# Power_Unit.net
KiCad netlist of a schematic drawn in Altium Designer
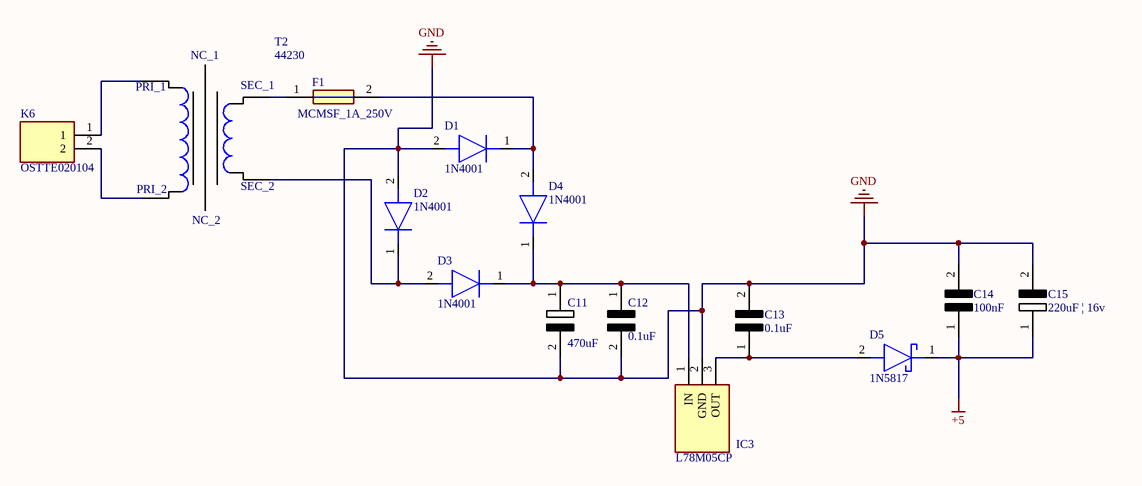
[diagram p0: Power_Unit.SchDoc]

(export (version "E")
  (design (tool "Eeschema 10.0.6"))
  (components
    (comp (ref "C11")
      (value "470uF")
      (footprint "C0805")
      (description "0805 ceramic capacitor")
      (fields
        (field (name "MANUFACTURER_PART_NUMBER") "GRM188R71H103KA01D")
        (field (name "MOUSER PART NUMBER") "81-GRM39X103K50D")
      )
      (libsource (lib "") (part "elektrolytischeC0805_1"))
    )
    (comp (ref "C12")
      (value "0.1uF")
      (footprint "C0805")
      (description "0805 ceramic capacitor")
      (fields
        (field (name "MANUFACTURER_PART_NUMBER") "GRM188R71H103KA01D")
        (field (name "MOUSER PART NUMBER") "81-GRM39X103K50D")
      )
      (libsource (lib "Schlib1") (part "KeramischeC0805_1"))
    )
    (comp (ref "C13")
      (value "0.1uF")
      (footprint "C0805")
      (description "0805 ceramic capacitor")
      (fields
        (field (name "MANUFACTURER_PART_NUMBER") "GRM188R71H103KA01D")
        (field (name "MOUSER PART NUMBER") "81-GRM39X103K50D")
      )
      (libsource (lib "") (part "KeramischeC0805_1_1"))
    )
    (comp (ref "C14")
      (value "100nF")
      (footprint "C0805")
      (description "0805 ceramic capacitor")
      (fields
        (field (name "MANUFACTURER_PART_NUMBER") "GRM188R71H103KA01D")
        (field (name "MOUSER PART NUMBER") "81-GRM39X103K50D")
      )
      (libsource (lib "") (part "KeramischeC0805_1_1"))
    )
    (comp (ref "C15")
      (value "220uF ¦ 16v")
      (footprint "C0805")
      (description "0805 ceramic capacitor")
      (fields
        (field (name "MANUFACTURER_PART_NUMBER") "GRM188R71H103KA01D")
        (field (name "MOUSER PART NUMBER") "81-GRM39X103K50D")
      )
      (libsource (lib "Schlib1") (part "elektrolytischeC0805"))
    )
    (comp (ref "D1")
      (value "1N4001")
      (footprint "SamacSys:DIOAD1405W86L465D235")
      (description "Diode")
      (libsource (lib "Schlib1") (part "1N4001"))
    )
    (comp (ref "D2")
      (value "1N4001")
      (footprint "SamacSys:DIOAD1405W86L465D235")
      (description "Diode")
      (libsource (lib "Schlib1") (part "1N4001"))
    )
    (comp (ref "D3")
      (value "1N4001")
      (footprint "SamacSys:DIOAD1405W86L465D235")
      (description "Diode")
      (libsource (lib "Schlib1") (part "1N4001"))
    )
    (comp (ref "D4")
      (value "1N4001")
      (footprint "SamacSys:DIOAD1405W86L465D235")
      (description "Diode")
      (libsource (lib "Schlib1") (part "1N4001"))
    )
    (comp (ref "D5")
      (value "1N5817")
      (footprint "1n5817_footprint")
      (description "Schottky Diode")
      (libsource (lib "Schlib1") (part "1N5817"))
    )
    (comp (ref "F1")
      (value "MCMSF_1A_250V")
      (footprint "SamacSys:MCMSF1A250V")
      (description "Fuse")
      (fields (field (name "MANUFACTURER_PART_NUMBER") "MCMSF 1A 250V"))
      (libsource (lib "Schlib1") (part "MCMSF_1A_250V"))
    )
    (comp (ref "IC3")
      (value "L78M05CP")
      (footprint "SamacSys:TO255P460X1020X2030-3P")
      (description "Integrated Circuit")
      (fields (field (name "MOUSER PART NUMBER") "511-L78M05CP"))
      (libsource (lib "Schlib1") (part "L78M05CP"))
    )
    (comp (ref "K6")
      (value "OSTTE020104")
      (footprint "SamacSys:OSTTE020104")
      (description "Connector")
      (libsource (lib "Schlib1") (part "OSTTE020104"))
    )
    (comp (ref "T2")
      (value "44230")
      (footprint "SamacSys:44230")
      (description "Transformer")
      (libsource (lib "Schlib1") (part "44230"))
    )
  )
  (nets
    (net (code "1") (name "+5") (class "Default")
      (node (ref "C14") (pin "1") (pinfunction "1_1") (pintype "passive"))
      (node (ref "C15") (pin "1") (pinfunction "1_1") (pintype "passive"))
      (node (ref "D5") (pin "1") (pinfunction "K_1") (pintype "passive"))
    )
    (net (code "2") (name "GND") (class "Default")
      (node (ref "C11") (pin "2") (pinfunction "2_2") (pintype "passive"))
      (node (ref "C12") (pin "2") (pinfunction "2_2") (pintype "passive"))
      (node (ref "C13") (pin "2") (pinfunction "2_2") (pintype "passive"))
      (node (ref "C14") (pin "2") (pinfunction "2_2") (pintype "passive"))
      (node (ref "C15") (pin "2") (pinfunction "2_2") (pintype "passive"))
      (node (ref "D1") (pin "2") (pinfunction "A_2") (pintype "passive"))
      (node (ref "D2") (pin "2") (pinfunction "A_2") (pintype "passive"))
      (node (ref "IC3") (pin "2") (pinfunction "GND_2") (pintype "power_in"))
    )
    (net (code "3") (name "Net-(D1-K)") (class "Default")
      (node (ref "D1") (pin "1") (pinfunction "K_1") (pintype "passive"))
      (node (ref "D4") (pin "2") (pinfunction "A_2") (pintype "passive"))
      (node (ref "F1") (pin "2") (pinfunction "2_2") (pintype "passive"))
    )
    (net (code "4") (name "Net-(D2-K)") (class "Default")
      (node (ref "D2") (pin "1") (pinfunction "K_1") (pintype "passive"))
      (node (ref "D3") (pin "2") (pinfunction "A_2") (pintype "passive"))
      (node (ref "T2") (pin "9") (pinfunction "SEC_2_9") (pintype "passive"))
    )
    (net (code "5") (name "Net-(D3-K)") (class "Default")
      (node (ref "C11") (pin "1") (pinfunction "1_1") (pintype "passive"))
      (node (ref "C12") (pin "1") (pinfunction "1_1") (pintype "passive"))
      (node (ref "D3") (pin "1") (pinfunction "K_1") (pintype "passive"))
      (node (ref "D4") (pin "1") (pinfunction "K_1") (pintype "passive"))
      (node (ref "IC3") (pin "1") (pinfunction "IN_1") (pintype "power_in"))
    )
    (net (code "6") (name "Net-(D5-A)") (class "Default")
      (node (ref "C13") (pin "1") (pinfunction "1_1") (pintype "passive"))
      (node (ref "D5") (pin "2") (pinfunction "A_2") (pintype "passive"))
      (node (ref "IC3") (pin "3") (pinfunction "OUT_3") (pintype "power_in"))
    )
    (net (code "7") (name "Net-(T2-PRI_1)") (class "Default")
      (node (ref "K6") (pin "1") (pinfunction "1_1") (pintype "passive"))
      (node (ref "T2") (pin "1") (pinfunction "PRI_1_1") (pintype "passive"))
    )
    (net (code "8") (name "Net-(T2-PRI_2)") (class "Default")
      (node (ref "K6") (pin "2") (pinfunction "2_2") (pintype "passive"))
      (node (ref "T2") (pin "5") (pinfunction "PRI_2_5") (pintype "passive"))
    )
    (net (code "9") (name "Net-(T2-SEC_1)") (class "Default")
      (node (ref "F1") (pin "1") (pinfunction "1_1") (pintype "passive"))
      (node (ref "T2") (pin "7") (pinfunction "SEC_1_7") (pintype "passive"))
    )
    (net (code "10") (name "unconnected-(T2-NC_1-Pad6)") (class "Default")
      (node (ref "T2") (pin "6") (pinfunction "NC_1_6") (pintype "passive"))
    )
    (net (code "11") (name "unconnected-(T2-NC_2-Pad10)") (class "Default")
      (node (ref "T2") (pin "10") (pinfunction "NC_2_10") (pintype "passive"))
    )
  )
)
